# Over_current_Over_voltage_Decoupling.net
KiCad netlist of a schematic drawn in EAGLE
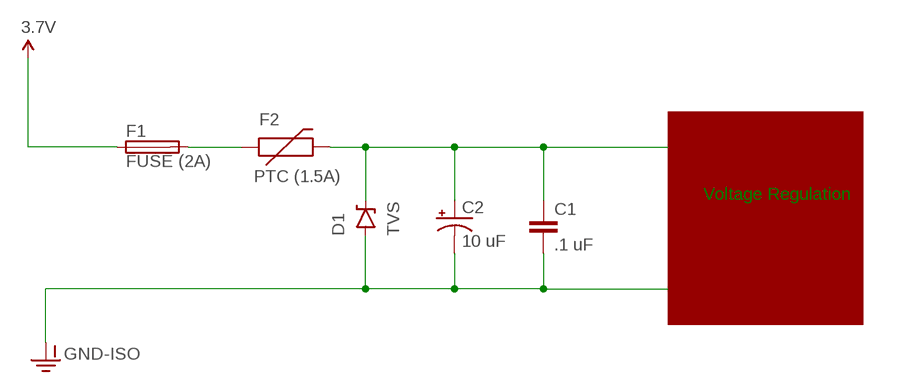
[diagram p0: schematic, sheet 1]

(export (version "E")
  (design (tool "Eeschema 10.0.6"))
  (components
    (comp (ref "C1")
      (value ".1 uF")
      (footprint "eagle-import:1206")
      (libsource (lib "eagle-import") (part "CAP1206"))
    )
    (comp (ref "C2")
      (value "10 uF")
      (footprint "eagle-import:CPOL-RADIAL-10UF-25V")
      (libsource (lib "eagle-import") (part "CAP_POLPTH2"))
    )
    (comp (ref "D1")
      (value "TVS")
      (footprint "eagle-import:DIODE-ZENER")
      (libsource (lib "eagle-import") (part "DIODE-ZENERPTH"))
    )
    (comp (ref "F1")
      (value "FUSE (2A)")
      (footprint "eagle-import:FUSE_HOLDER_MENTOR-1821")
      (libsource (lib "eagle-import") (part "FUSE1821"))
    )
    (comp (ref "F2")
      (value "PTC (1.5A)")
      (footprint "eagle-import:PTC")
      (libsource (lib "eagle-import") (part "PTCPTH"))
    )
  )
  (nets
    (net (code "1") (name "3.7V") (class "Default")
      (node (ref "F1") (pin "A") (pinfunction "1_A") (pintype "passive"))
    )
    (net (code "2") (name "GND-ISO") (class "Default")
      (node (ref "C1") (pin "2") (pinfunction "2_2") (pintype "passive"))
      (node (ref "C2") (pin "2") (pinfunction "-_2") (pintype "passive"))
      (node (ref "D1") (pin "P$2") (pinfunction "A_P$2") (pintype "passive"))
    )
    (net (code "3") (name "Net-(C2-+)") (class "Default")
      (node (ref "C1") (pin "1") (pinfunction "1_1") (pintype "passive"))
      (node (ref "C2") (pin "1") (pinfunction "+_1") (pintype "passive"))
      (node (ref "D1") (pin "P$1") (pinfunction "C_P$1") (pintype "passive"))
      (node (ref "F2") (pin "P$2") (pinfunction "2_P$2") (pintype "bidirectional"))
    )
    (net (code "4") (name "Net-(F1-2)") (class "Default")
      (node (ref "F1") (pin "B") (pinfunction "2_B") (pintype "passive"))
      (node (ref "F2") (pin "P$1") (pinfunction "1_P$1") (pintype "bidirectional"))
    )
  )
)
